# 11_-_Power_Input_and_Regulators.net
KiCad netlist of a schematic drawn in Altium Designer
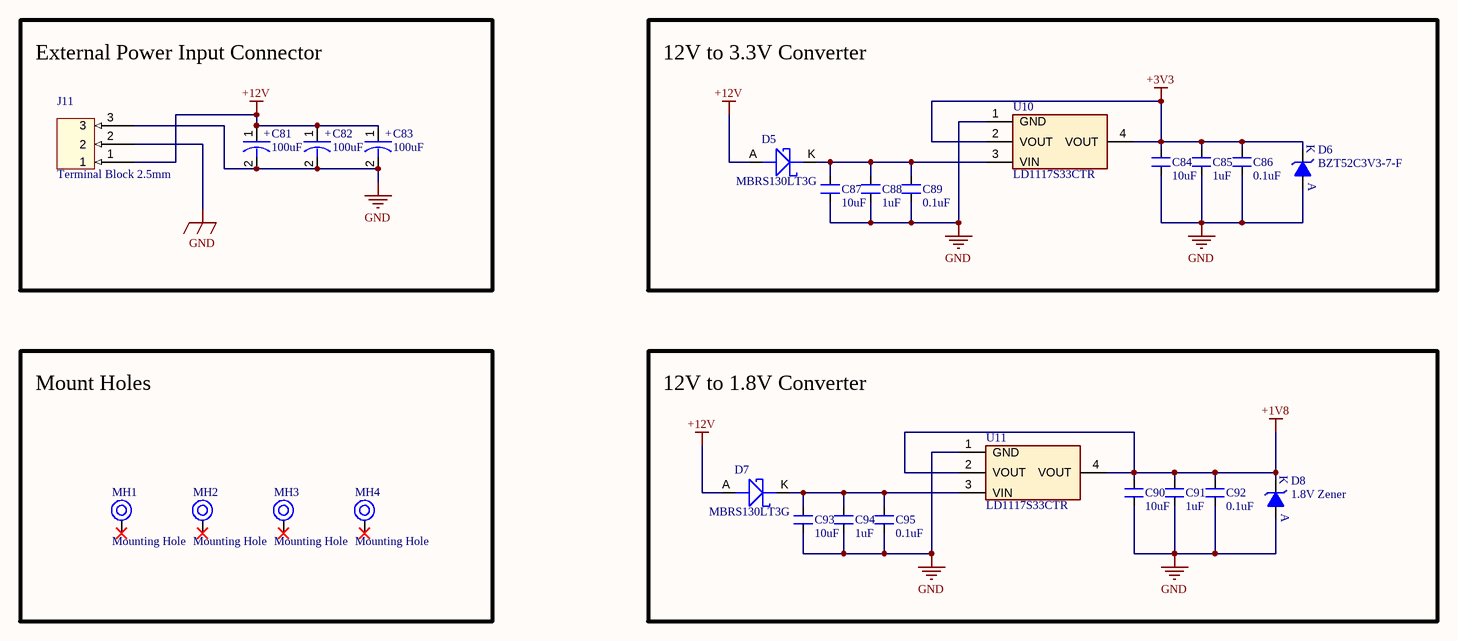
[diagram p0: [11] - Power Input and Regulators.SchDoc]

(export (version "E")
  (design (tool "Eeschema 10.0.6"))
  (components
    (comp (ref "C81")
      (value "100uF")
      (footprint "ACAP_P305_D393_H393_RAD")
      (description "100µF 50V Aluminum Polymer Capacitor Radial, Can - SMD 28mOhm 4000 Hrs @ 125°C")
      (fields
        (field (name "MANUFACTURER") "Nichicon")
        (field (name "MANUFACTURER PART NUMBER") "GYA1H101MCQ1GS")
      )
      (libsource (lib "ESTEEMPCBLIB") (part "CAP-P_100uF-50V-20%-RAD"))
    )
    (comp (ref "C82")
      (value "100uF")
      (footprint "ACAP_P305_D393_H393_RAD")
      (description "100µF 50V Aluminum Polymer Capacitor Radial, Can - SMD 28mOhm 4000 Hrs @ 125°C")
      (fields
        (field (name "MANUFACTURER") "Nichicon")
        (field (name "MANUFACTURER PART NUMBER") "GYA1H101MCQ1GS")
      )
      (libsource (lib "ESTEEMPCBLIB") (part "CAP-P_100uF-50V-20%-RAD"))
    )
    (comp (ref "C83")
      (value "100uF")
      (footprint "ACAP_P305_D393_H393_RAD")
      (description "100µF 50V Aluminum Polymer Capacitor Radial, Can - SMD 28mOhm 4000 Hrs @ 125°C")
      (fields
        (field (name "MANUFACTURER") "Nichicon")
        (field (name "MANUFACTURER PART NUMBER") "GYA1H101MCQ1GS")
      )
      (libsource (lib "ESTEEMPCBLIB") (part "CAP-P_100uF-50V-20%-RAD"))
    )
    (comp (ref "C84")
      (value "10uF")
      (footprint "CAP_1206")
      (description "10µF ±10% 50V Ceramic Capacitor X7R 1206 (3216 Metric)")
      (fields
        (field (name "MANUFACTURER") "KEMET")
        (field (name "MANUFACTURER PART NUMBER") "CL31B106KBHNNNE")
      )
      (libsource (lib "ESTEEMPCBLIB") (part "CAP_10uF-50V-10%-1206"))
    )
    (comp (ref "C85")
      (value "1uF")
      (footprint "CAP_0805")
      (description "1µF ±5% 50V Ceramic Capacitor X7R 0805 (2012 Metric)")
      (fields
        (field (name "MANUFACTURER") "Samsung")
        (field (name "MANUFACTURER PART NUMBER") "CC0805JKX7R9BB105")
      )
      (libsource (lib "ESTEEMPCBLIB") (part "CAP_1uF-50V-5%-0805"))
    )
    (comp (ref "C86")
      (value "0.1uF")
      (footprint "CAP_0805")
      (description "0.1µF ±10% 50V Ceramic Capacitor X7R 0805 (2012 Metric)")
      (fields
        (field (name "MANUFACTURER") "Samsung")
        (field (name "MANUFACTURER PART NUMBER") "CL21B104KBCNNNC")
      )
      (libsource (lib "ESTEEMPCBLIB") (part "CAP_0.1uF-50V-10%-0805"))
    )
    (comp (ref "C87")
      (value "10uF")
      (footprint "CAP_1206")
      (description "10µF ±10% 50V Ceramic Capacitor X7R 1206 (3216 Metric)")
      (fields
        (field (name "MANUFACTURER") "KEMET")
        (field (name "MANUFACTURER PART NUMBER") "CL31B106KBHNNNE")
      )
      (libsource (lib "ESTEEMPCBLIB") (part "CAP_10uF-50V-10%-1206"))
    )
    (comp (ref "C88")
      (value "1uF")
      (footprint "CAP_0805")
      (description "1µF ±5% 50V Ceramic Capacitor X7R 0805 (2012 Metric)")
      (fields
        (field (name "MANUFACTURER") "Samsung")
        (field (name "MANUFACTURER PART NUMBER") "CC0805JKX7R9BB105")
      )
      (libsource (lib "ESTEEMPCBLIB") (part "CAP_1uF-50V-5%-0805"))
    )
    (comp (ref "C89")
      (value "0.1uF")
      (footprint "CAP_0805")
      (description "0.1µF ±10% 50V Ceramic Capacitor X7R 0805 (2012 Metric)")
      (fields
        (field (name "MANUFACTURER") "Samsung")
        (field (name "MANUFACTURER PART NUMBER") "CL21B104KBCNNNC")
      )
      (libsource (lib "ESTEEMPCBLIB") (part "CAP_0.1uF-50V-10%-0805"))
    )
    (comp (ref "C90")
      (value "10uF")
      (footprint "CAP_1206")
      (description "10µF ±10% 50V Ceramic Capacitor X7R 1206 (3216 Metric)")
      (fields
        (field (name "MANUFACTURER") "KEMET")
        (field (name "MANUFACTURER PART NUMBER") "CL31B106KBHNNNE")
      )
      (libsource (lib "ESTEEMPCBLIB") (part "CAP_10uF-50V-10%-1206"))
    )
    (comp (ref "C91")
      (value "1uF")
      (footprint "CAP_0805")
      (description "1µF ±5% 50V Ceramic Capacitor X7R 0805 (2012 Metric)")
      (fields
        (field (name "MANUFACTURER") "Samsung")
        (field (name "MANUFACTURER PART NUMBER") "CC0805JKX7R9BB105")
      )
      (libsource (lib "ESTEEMPCBLIB") (part "CAP_1uF-50V-5%-0805"))
    )
    (comp (ref "C92")
      (value "0.1uF")
      (footprint "CAP_0805")
      (description "0.1µF ±10% 50V Ceramic Capacitor X7R 0805 (2012 Metric)")
      (fields
        (field (name "MANUFACTURER") "Samsung")
        (field (name "MANUFACTURER PART NUMBER") "CL21B104KBCNNNC")
      )
      (libsource (lib "ESTEEMPCBLIB") (part "CAP_0.1uF-50V-10%-0805"))
    )
    (comp (ref "C93")
      (value "10uF")
      (footprint "CAP_1206")
      (description "10µF ±10% 50V Ceramic Capacitor X7R 1206 (3216 Metric)")
      (fields
        (field (name "MANUFACTURER") "KEMET")
        (field (name "MANUFACTURER PART NUMBER") "CL31B106KBHNNNE")
      )
      (libsource (lib "ESTEEMPCBLIB") (part "CAP_10uF-50V-10%-1206"))
    )
    (comp (ref "C94")
      (value "1uF")
      (footprint "CAP_0805")
      (description "1µF ±5% 50V Ceramic Capacitor X7R 0805 (2012 Metric)")
      (fields
        (field (name "MANUFACTURER") "Samsung")
        (field (name "MANUFACTURER PART NUMBER") "CC0805JKX7R9BB105")
      )
      (libsource (lib "ESTEEMPCBLIB") (part "CAP_1uF-50V-5%-0805"))
    )
    (comp (ref "C95")
      (value "0.1uF")
      (footprint "CAP_0805")
      (description "0.1µF ±10% 50V Ceramic Capacitor X7R 0805 (2012 Metric)")
      (fields
        (field (name "MANUFACTURER") "Samsung")
        (field (name "MANUFACTURER PART NUMBER") "CL21B104KBCNNNC")
      )
      (libsource (lib "ESTEEMPCBLIB") (part "CAP_0.1uF-50V-10%-0805"))
    )
    (comp (ref "D5")
      (value "MBRS130LT3G")
      (footprint "DIO_SMB_DO-214AA")
      (description "Diode Schottky 30V 2A Surface Mount SMB")
      (fields (field (name "MANUFACTURER") "ON Semiconductor"))
      (libsource (lib "ESTEEMPCBLIB") (part "DIO-S_445mV-30V-2A-SMB"))
    )
    (comp (ref "D6")
      (value "BZT52C3V3-7-F")
      (footprint "DIO_SOD-123")
      (description "Zener Diode 3.3V 500mW ±6% Surface Mount SOD-123")
      (fields (field (name "MANUFACTURER") "Diodes Incorporated"))
      (libsource (lib "ESTEEMPCBLIB") (part "DIO-Z_3.3V-500mW-SOD123"))
    )
    (comp (ref "D7")
      (value "MBRS130LT3G")
      (footprint "DIO_SMB_DO-214AA")
      (description "Diode Schottky 30V 2A Surface Mount SMB")
      (fields (field (name "MANUFACTURER") "ON Semiconductor"))
      (libsource (lib "ESTEEMPCBLIB") (part "DIO-S_445mV-30V-2A-SMB"))
    )
    (comp (ref "D8")
      (value "1.8V Zener")
      (footprint "DIO_DO-213AB_SMD")
      (description "Zener Diode 1.8V 500mW ±5% Surface Mount DO-213AA")
      (libsource (lib "ESTEEMPCBLIB") (part "DIO-Z_1.8V-500mW-DO213AA"))
    )
    (comp (ref "J11")
      (value "Terminal Block 2.5mm")
      (footprint "CON3_100_TB_TH_ST")
      (description "3 Pins, 1 Row 2.54mm Pitch, straight Connector, male")
      (fields
        (field (name "MANUFACTURER PART NUMBER") "1725669")
        (field (name "MANUFACTURER") "Phoenix Contact")
      )
      (libsource (lib "ESTEEMPCBLIB") (part "CON-TB_3X1-100-ST-TH"))
    )
    (comp (ref "MH1")
      (value "Mounting Hole")
      (footprint "MOUNTING")
      (fields (field (name "MANUFACTURER PART NUMBER") "NA"))
      (libsource (lib "ESTEEMPCBLIB") (part "MH_3.5H_6D"))
    )
    (comp (ref "MH2")
      (value "Mounting Hole")
      (footprint "MOUNTING")
      (fields (field (name "MANUFACTURER PART NUMBER") "NA"))
      (libsource (lib "ESTEEMPCBLIB") (part "MH_3.5H_6D"))
    )
    (comp (ref "MH3")
      (value "Mounting Hole")
      (footprint "MOUNTING")
      (fields (field (name "MANUFACTURER PART NUMBER") "NA"))
      (libsource (lib "ESTEEMPCBLIB") (part "MH_3.5H_6D"))
    )
    (comp (ref "MH4")
      (value "Mounting Hole")
      (footprint "MOUNTING")
      (fields (field (name "MANUFACTURER PART NUMBER") "NA"))
      (libsource (lib "ESTEEMPCBLIB") (part "MH_3.5H_6D"))
    )
    (comp (ref "U10")
      (value "LD1117S33CTR")
      (footprint "SOT223_3")
      (description "Linear Voltage Regulator IC 1 Output 800mA SOT-223")
      (fields (field (name "MANUFACTURER") "STMicroelectronics"))
      (libsource (lib "ESTEEMPCBLIB") (part "REG_15V-3.3V-0.9A-12W-SOT223"))
    )
    (comp (ref "U11")
      (value "LD1117S33CTR")
      (footprint "SOT223_3")
      (description "Linear Voltage Regulator IC 1 Output 800mA SOT-223")
      (fields (field (name "MANUFACTURER") "STMicroelectronics"))
      (libsource (lib "ESTEEMPCBLIB") (part "REG_15V-3.3V-0.9A-12W-SOT223"))
    )
  )
  (nets
    (net (code "1") (name "+1V8") (class "Default")
      (node (ref "C90") (pin "2") (pinfunction "2_2") (pintype "passive"))
      (node (ref "C91") (pin "2") (pinfunction "2_2") (pintype "passive"))
      (node (ref "C92") (pin "2") (pinfunction "2_2") (pintype "passive"))
      (node (ref "D8") (pin "K") (pinfunction "K_K") (pintype "passive"))
      (node (ref "U11") (pin "2") (pinfunction "VOUT_2") (pintype "passive"))
      (node (ref "U11") (pin "4") (pinfunction "VOUT_4") (pintype "passive"))
    )
    (net (code "2") (name "+3V3") (class "Default")
      (node (ref "C84") (pin "2") (pinfunction "2_2") (pintype "passive"))
      (node (ref "C85") (pin "2") (pinfunction "2_2") (pintype "passive"))
      (node (ref "C86") (pin "2") (pinfunction "2_2") (pintype "passive"))
      (node (ref "D6") (pin "K") (pinfunction "K_K") (pintype "passive"))
      (node (ref "U10") (pin "2") (pinfunction "VOUT_2") (pintype "passive"))
      (node (ref "U10") (pin "4") (pinfunction "VOUT_4") (pintype "passive"))
    )
    (net (code "3") (name "+12V") (class "Default")
      (node (ref "C81") (pin "1") (pinfunction "1_1") (pintype "passive"))
      (node (ref "C82") (pin "1") (pinfunction "1_1") (pintype "passive"))
      (node (ref "C83") (pin "1") (pinfunction "1_1") (pintype "passive"))
      (node (ref "D5") (pin "A") (pinfunction "A_A") (pintype "passive"))
      (node (ref "D7") (pin "A") (pinfunction "A_A") (pintype "passive"))
      (node (ref "J11") (pin "1") (pinfunction "1_1") (pintype "input"))
    )
    (net (code "4") (name "GND") (class "Default")
      (node (ref "C81") (pin "2") (pinfunction "2_2") (pintype "passive"))
      (node (ref "C82") (pin "2") (pinfunction "2_2") (pintype "passive"))
      (node (ref "C83") (pin "2") (pinfunction "2_2") (pintype "passive"))
      (node (ref "C84") (pin "1") (pinfunction "1_1") (pintype "passive"))
      (node (ref "C85") (pin "1") (pinfunction "1_1") (pintype "passive"))
      (node (ref "C86") (pin "1") (pinfunction "1_1") (pintype "passive"))
      (node (ref "C87") (pin "1") (pinfunction "1_1") (pintype "passive"))
      (node (ref "C88") (pin "1") (pinfunction "1_1") (pintype "passive"))
      (node (ref "C89") (pin "1") (pinfunction "1_1") (pintype "passive"))
      (node (ref "C90") (pin "1") (pinfunction "1_1") (pintype "passive"))
      (node (ref "C91") (pin "1") (pinfunction "1_1") (pintype "passive"))
      (node (ref "C92") (pin "1") (pinfunction "1_1") (pintype "passive"))
      (node (ref "C93") (pin "1") (pinfunction "1_1") (pintype "passive"))
      (node (ref "C94") (pin "1") (pinfunction "1_1") (pintype "passive"))
      (node (ref "C95") (pin "1") (pinfunction "1_1") (pintype "passive"))
      (node (ref "D6") (pin "A") (pinfunction "A_A") (pintype "passive"))
      (node (ref "D8") (pin "A") (pinfunction "A_A") (pintype "passive"))
      (node (ref "J11") (pin "2") (pinfunction "2_2") (pintype "input"))
      (node (ref "J11") (pin "3") (pinfunction "3_3") (pintype "input"))
      (node (ref "U10") (pin "1") (pinfunction "GND_1") (pintype "passive"))
      (node (ref "U11") (pin "1") (pinfunction "GND_1") (pintype "passive"))
    )
    (net (code "5") (name "Net-(U10-VIN)") (class "Default")
      (node (ref "C87") (pin "2") (pinfunction "2_2") (pintype "passive"))
      (node (ref "C88") (pin "2") (pinfunction "2_2") (pintype "passive"))
      (node (ref "C89") (pin "2") (pinfunction "2_2") (pintype "passive"))
      (node (ref "D5") (pin "K") (pinfunction "K_K") (pintype "passive"))
      (node (ref "U10") (pin "3") (pinfunction "VIN_3") (pintype "passive"))
    )
    (net (code "6") (name "Net-(U11-VIN)") (class "Default")
      (node (ref "C93") (pin "2") (pinfunction "2_2") (pintype "passive"))
      (node (ref "C94") (pin "2") (pinfunction "2_2") (pintype "passive"))
      (node (ref "C95") (pin "2") (pinfunction "2_2") (pintype "passive"))
      (node (ref "D7") (pin "K") (pinfunction "K_K") (pintype "passive"))
      (node (ref "U11") (pin "3") (pinfunction "VIN_3") (pintype "passive"))
    )
    (net (code "7") (name "unconnected-(MH1-Pad1)") (class "Default")
      (node (ref "MH1") (pin "1") (pinfunction "1_1") (pintype "passive+no_connect"))
    )
    (net (code "8") (name "unconnected-(MH2-Pad1)") (class "Default")
      (node (ref "MH2") (pin "1") (pinfunction "1_1") (pintype "passive+no_connect"))
    )
    (net (code "9") (name "unconnected-(MH3-Pad1)") (class "Default")
      (node (ref "MH3") (pin "1") (pinfunction "1_1") (pintype "passive+no_connect"))
    )
    (net (code "10") (name "unconnected-(MH4-Pad1)") (class "Default")
      (node (ref "MH4") (pin "1") (pinfunction "1_1") (pintype "passive+no_connect"))
    )
  )
)
